# new_base_sensor_1.net
KiCad netlist of a schematic drawn in Altium Designer
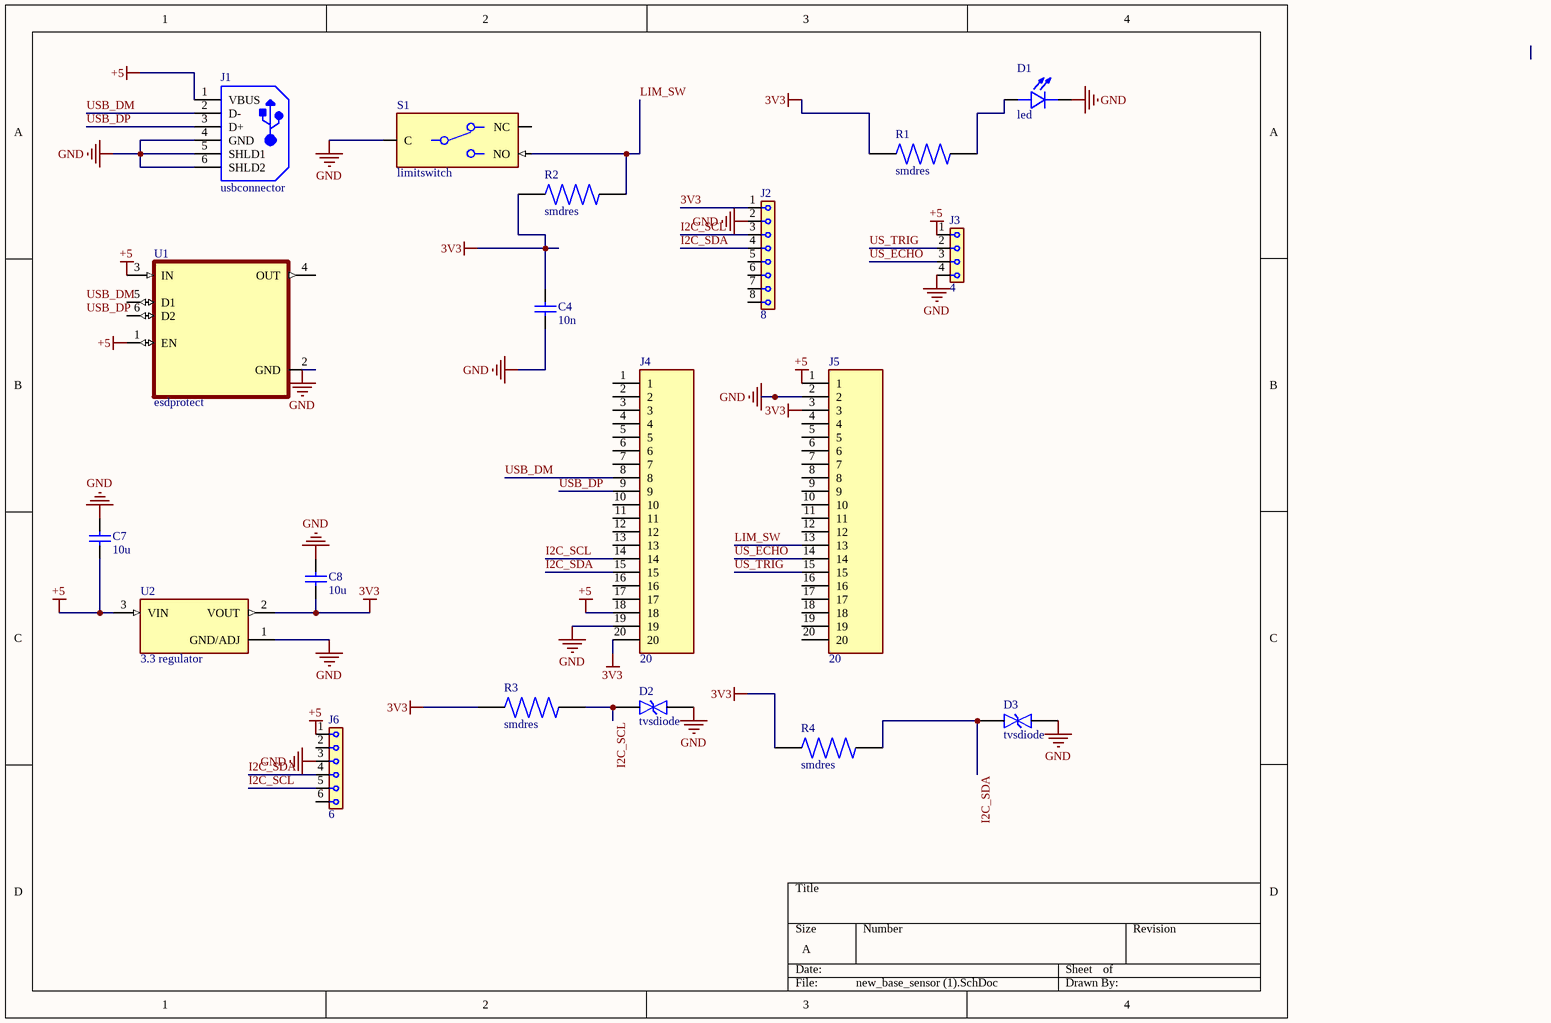
[diagram p0: new_base_sensor (1).SchDoc]

(export (version "E")
  (design (tool "Eeschema 10.0.6"))
  (components
    (comp (ref "C4")
      (value "10n")
      (description "Capacitor")
      (libsource (lib "Simulation Generic Components") (part "Capacitor"))
    )
    (comp (ref "C7")
      (value "10u")
      (description "Capacitor")
      (libsource (lib "Simulation Generic Components") (part "Capacitor"))
    )
    (comp (ref "C8")
      (value "10u")
      (description "Capacitor")
      (libsource (lib "Simulation Generic Components") (part "Capacitor"))
    )
    (comp (ref "D1")
      (value "led")
      (footprint "led")
      (description "Green 1.6 x 0.8 x 0.75 mm (0603) 120 潞 180 mcd Water Clear SMT LED")
      (fields (field (name "MF") "Kingbright") (field (name "MP") "APT1608VGC/A"))
      (libsource (lib "base_sensors") (part "led"))
    )
    (comp (ref "D2")
      (value "tvsdiode")
      (footprint "tvsdiode")
      (description "59V Clamp 169A (8/20Âµs) Ipp Tvs Diode Through Hole DO-201")
      (fields (field (name "MF") "STMicroelectronics") (field (name "MP") "1.5KE33CA"))
      (libsource (lib "base_sensors") (part "tvsdiode"))
    )
    (comp (ref "D3")
      (value "tvsdiode")
      (footprint "tvsdiode")
      (description "59V Clamp 169A (8/20Âµs) Ipp Tvs Diode Through Hole DO-201")
      (fields (field (name "MF") "STMicroelectronics") (field (name "MP") "1.5KE33CA"))
      (libsource (lib "base_sensors") (part "tvsdiode"))
    )
    (comp (ref "J1")
      (value "usbconnector")
      (footprint "usbconnector")
      (description "Single USB 2.0, Receptacle Connecter, B Type, 4 Position Through Hole, -55 to 85 degC, RoHS, Tray")
      (libsource (lib "Actuator_Base_Board") (part "CMP-1752-00001-1"))
    )
    (comp (ref "J2")
      (value "8")
      (footprint "8")
      (fields (field (name "MF") "WÃ¼rth Elektronik") (field (name "MP") "62001011821"))
      (libsource (lib "base_sensors") (part "8"))
    )
    (comp (ref "J3")
      (value "4")
      (footprint "4")
      (fields (field (name "MF") "WÃ¼rth Elektronik") (field (name "MP") "62001011821"))
      (libsource (lib "base_sensors") (part "4"))
    )
    (comp (ref "J4")
      (value "20")
      (footprint "20")
      (description "AMPMODU 20 Position Through-Hole Single Row Straight .100 Inch Header")
      (fields (field (name "MF") "TE Connectivity") (field (name "MP") "2-87224-0"))
      (libsource (lib "base_sensors") (part "20"))
    )
    (comp (ref "J5")
      (value "20")
      (footprint "20")
      (description "AMPMODU 20 Position Through-Hole Single Row Straight .100 Inch Header")
      (fields (field (name "MF") "TE Connectivity") (field (name "MP") "2-87224-0"))
      (libsource (lib "base_sensors") (part "20"))
    )
    (comp (ref "J6")
      (value "6")
      (footprint "6")
      (fields (field (name "MF") "WÃ¼rth Elektronik") (field (name "MP") "62001011821"))
      (libsource (lib "base_sensors") (part "6"))
    )
    (comp (ref "R1")
      (value "smdres")
      (footprint "smdres")
      (description "RES SMD 470 OHM 1% 1/10W 0603")
      (fields (field (name "MF") "Panasonic") (field (name "MP") "ERJS03F4700V"))
      (libsource (lib "new_base_sensors") (part "smdres"))
    )
    (comp (ref "R2")
      (value "smdres")
      (footprint "smdres")
      (description "RES SMD 470 OHM 1% 1/10W 0603")
      (fields (field (name "MF") "Panasonic") (field (name "MP") "ERJS03F4700V"))
      (libsource (lib "new_base_sensors") (part "smdres"))
    )
    (comp (ref "R3")
      (value "smdres")
      (footprint "smdres")
      (description "RES SMD 470 OHM 1% 1/10W 0603")
      (fields (field (name "MF") "Panasonic") (field (name "MP") "ERJS03F4700V"))
      (libsource (lib "new_base_sensors") (part "smdres"))
    )
    (comp (ref "R4")
      (value "smdres")
      (footprint "smdres")
      (description "RES SMD 470 OHM 1% 1/10W 0603")
      (fields (field (name "MF") "Panasonic") (field (name "MP") "ERJS03F4700V"))
      (libsource (lib "new_base_sensors") (part "smdres"))
    )
    (comp (ref "S1")
      (value "limitswitch")
      (footprint "limitswitch")
      (description "Switch Snap Action N.O./N.C. SPDT Long Hinge Lever Solder 5A 250VAC 0.39N Screw Mount")
      (fields (field (name "MF") "Omron") (field (name "MP") "SS-5GL111"))
      (libsource (lib "base_sensors") (part "limitswitch"))
    )
    (comp (ref "U1")
      (value "esdprotect")
      (footprint "esdprotect")
      (description "Current-limit switch and D+/Dâ€“ ESD protection for USB Host")
      (fields (field (name "MF") "Texas Instruments") (field (name "MP") "TPD3S044DBVR"))
      (libsource (lib "base_sensors") (part "esdprotect"))
    )
    (comp (ref "U2")
      (value "3.3 regulator")
      (footprint "3.3regultor")
      (description "LDO Voltage Regulators 800MA LDO LINEAR REG")
      (fields (field (name "MF") "ams AG") (field (name "MP") "AMS1117-3.3"))
      (libsource (lib "base_sensors") (part "3.3 regulator"))
    )
  )
  (nets
    (net (code "1") (name "+5") (class "Default")
      (node (ref "C7") (pin "1") (pinfunction "1_1") (pintype "passive"))
      (node (ref "J1") (pin "1") (pinfunction "VBUS_1") (pintype "passive"))
      (node (ref "J3") (pin "1") (pinfunction "1_1") (pintype "passive"))
      (node (ref "J4") (pin "18") (pinfunction "18_18") (pintype "passive"))
      (node (ref "J5") (pin "1") (pinfunction "1_1") (pintype "passive"))
      (node (ref "J6") (pin "1") (pinfunction "1_1") (pintype "passive"))
      (node (ref "U1") (pin "1") (pinfunction "EN_1") (pintype "bidirectional"))
      (node (ref "U1") (pin "3") (pinfunction "IN_3") (pintype "input"))
      (node (ref "U2") (pin "3") (pinfunction "VIN_3") (pintype "input"))
    )
    (net (code "2") (name "/I2C_SCL") (class "Default")
      (node (ref "D2") (pin "1") (pinfunction "1_1") (pintype "passive"))
      (node (ref "J2") (pin "3") (pinfunction "3_3") (pintype "passive"))
      (node (ref "J4") (pin "14") (pinfunction "14_14") (pintype "passive"))
      (node (ref "J6") (pin "5") (pinfunction "5_5") (pintype "passive"))
      (node (ref "R3") (pin "0") (pinfunction "0_0") (pintype "passive"))
    )
    (net (code "3") (name "/I2C_SDA") (class "Default")
      (node (ref "D3") (pin "1") (pinfunction "1_1") (pintype "passive"))
      (node (ref "J2") (pin "4") (pinfunction "4_4") (pintype "passive"))
      (node (ref "J4") (pin "15") (pinfunction "15_15") (pintype "passive"))
      (node (ref "J6") (pin "4") (pinfunction "4_4") (pintype "passive"))
      (node (ref "R4") (pin "0") (pinfunction "0_0") (pintype "passive"))
    )
    (net (code "4") (name "/LIM_SW") (class "Default")
      (node (ref "J5") (pin "13") (pinfunction "13_13") (pintype "passive"))
      (node (ref "R2") (pin "0") (pinfunction "0_0") (pintype "passive"))
      (node (ref "S1") (pin "NO") (pinfunction "NO_NO") (pintype "input"))
    )
    (net (code "5") (name "/USB_DM") (class "Default")
      (node (ref "J1") (pin "2") (pinfunction "D-_2") (pintype "passive"))
      (node (ref "J4") (pin "8") (pinfunction "8_8") (pintype "passive"))
    )
    (net (code "6") (name "/USB_DP") (class "Default")
      (node (ref "J1") (pin "3") (pinfunction "D+_3") (pintype "passive"))
      (node (ref "J4") (pin "9") (pinfunction "9_9") (pintype "passive"))
    )
    (net (code "7") (name "/US_ECHO") (class "Default")
      (node (ref "J3") (pin "3") (pinfunction "3_3") (pintype "passive"))
      (node (ref "J5") (pin "14") (pinfunction "14_14") (pintype "passive"))
    )
    (net (code "8") (name "/US_TRIG") (class "Default")
      (node (ref "J3") (pin "2") (pinfunction "2_2") (pintype "passive"))
      (node (ref "J5") (pin "15") (pinfunction "15_15") (pintype "passive"))
    )
    (net (code "9") (name "3V3") (class "Default")
      (node (ref "C4") (pin "1") (pinfunction "1_1") (pintype "passive"))
      (node (ref "C8") (pin "1") (pinfunction "1_1") (pintype "passive"))
      (node (ref "J2") (pin "1") (pinfunction "1_1") (pintype "passive"))
      (node (ref "J4") (pin "20") (pinfunction "20_20") (pintype "passive"))
      (node (ref "J5") (pin "3") (pinfunction "3_3") (pintype "passive"))
      (node (ref "R1") (pin "1") (pinfunction "1_1") (pintype "passive"))
      (node (ref "R2") (pin "1") (pinfunction "1_1") (pintype "passive"))
      (node (ref "R3") (pin "1") (pinfunction "1_1") (pintype "passive"))
      (node (ref "R4") (pin "1") (pinfunction "1_1") (pintype "passive"))
      (node (ref "U2") (pin "2") (pinfunction "VOUT_2") (pintype "output"))
    )
    (net (code "10") (name "GND") (class "Default")
      (node (ref "C4") (pin "2") (pinfunction "2_2") (pintype "passive"))
      (node (ref "C7") (pin "2") (pinfunction "2_2") (pintype "passive"))
      (node (ref "C8") (pin "2") (pinfunction "2_2") (pintype "passive"))
      (node (ref "D1") (pin "C") (pinfunction "C_C") (pintype "passive"))
      (node (ref "D2") (pin "2") (pinfunction "2_2") (pintype "passive"))
      (node (ref "D3") (pin "2") (pinfunction "2_2") (pintype "passive"))
      (node (ref "J1") (pin "4") (pinfunction "GND_4") (pintype "passive"))
      (node (ref "J1") (pin "5") (pinfunction "SHLD1_5") (pintype "passive"))
      (node (ref "J1") (pin "6") (pinfunction "SHLD2_6") (pintype "passive"))
      (node (ref "J2") (pin "2") (pinfunction "2_2") (pintype "passive"))
      (node (ref "J3") (pin "4") (pinfunction "4_4") (pintype "passive"))
      (node (ref "J4") (pin "19") (pinfunction "19_19") (pintype "passive"))
      (node (ref "J5") (pin "2") (pinfunction "2_2") (pintype "passive"))
      (node (ref "J6") (pin "3") (pinfunction "3_3") (pintype "passive"))
      (node (ref "S1") (pin "C") (pinfunction "C_C") (pintype "bidirectional"))
      (node (ref "U1") (pin "2") (pinfunction "GND_2") (pintype "power_in"))
      (node (ref "U2") (pin "1") (pinfunction "GND/ADJ_1") (pintype "power_in"))
    )
    (net (code "11") (name "Net-(D1-PadA)") (class "Default")
      (node (ref "D1") (pin "A") (pinfunction "A_A") (pintype "passive"))
      (node (ref "R1") (pin "0") (pinfunction "0_0") (pintype "passive"))
    )
    (net (code "12") (name "unconnected-(J2-Pad5)") (class "Default")
      (node (ref "J2") (pin "5") (pinfunction "5_5") (pintype "passive"))
    )
    (net (code "13") (name "unconnected-(J2-Pad6)") (class "Default")
      (node (ref "J2") (pin "6") (pinfunction "6_6") (pintype "passive"))
    )
    (net (code "14") (name "unconnected-(J2-Pad7)") (class "Default")
      (node (ref "J2") (pin "7") (pinfunction "7_7") (pintype "passive"))
    )
    (net (code "15") (name "unconnected-(J2-Pad8)") (class "Default")
      (node (ref "J2") (pin "8") (pinfunction "8_8") (pintype "passive"))
    )
    (net (code "16") (name "unconnected-(J4-Pad1)") (class "Default")
      (node (ref "J4") (pin "1") (pinfunction "1_1") (pintype "passive"))
    )
    (net (code "17") (name "unconnected-(J4-Pad2)") (class "Default")
      (node (ref "J4") (pin "2") (pinfunction "2_2") (pintype "passive"))
    )
    (net (code "18") (name "unconnected-(J4-Pad3)") (class "Default")
      (node (ref "J4") (pin "3") (pinfunction "3_3") (pintype "passive"))
    )
    (net (code "19") (name "unconnected-(J4-Pad4)") (class "Default")
      (node (ref "J4") (pin "4") (pinfunction "4_4") (pintype "passive"))
    )
    (net (code "20") (name "unconnected-(J4-Pad5)") (class "Default")
      (node (ref "J4") (pin "5") (pinfunction "5_5") (pintype "passive"))
    )
    (net (code "21") (name "unconnected-(J4-Pad6)") (class "Default")
      (node (ref "J4") (pin "6") (pinfunction "6_6") (pintype "passive"))
    )
    (net (code "22") (name "unconnected-(J4-Pad7)") (class "Default")
      (node (ref "J4") (pin "7") (pinfunction "7_7") (pintype "passive"))
    )
    (net (code "23") (name "unconnected-(J4-Pad10)") (class "Default")
      (node (ref "J4") (pin "10") (pinfunction "10_10") (pintype "passive"))
    )
    (net (code "24") (name "unconnected-(J4-Pad11)") (class "Default")
      (node (ref "J4") (pin "11") (pinfunction "11_11") (pintype "passive"))
    )
    (net (code "25") (name "unconnected-(J4-Pad12)") (class "Default")
      (node (ref "J4") (pin "12") (pinfunction "12_12") (pintype "passive"))
    )
    (net (code "26") (name "unconnected-(J4-Pad13)") (class "Default")
      (node (ref "J4") (pin "13") (pinfunction "13_13") (pintype "passive"))
    )
    (net (code "27") (name "unconnected-(J4-Pad16)") (class "Default")
      (node (ref "J4") (pin "16") (pinfunction "16_16") (pintype "passive"))
    )
    (net (code "28") (name "unconnected-(J4-Pad17)") (class "Default")
      (node (ref "J4") (pin "17") (pinfunction "17_17") (pintype "passive"))
    )
    (net (code "29") (name "unconnected-(J5-Pad4)") (class "Default")
      (node (ref "J5") (pin "4") (pinfunction "4_4") (pintype "passive"))
    )
    (net (code "30") (name "unconnected-(J5-Pad5)") (class "Default")
      (node (ref "J5") (pin "5") (pinfunction "5_5") (pintype "passive"))
    )
    (net (code "31") (name "unconnected-(J5-Pad6)") (class "Default")
      (node (ref "J5") (pin "6") (pinfunction "6_6") (pintype "passive"))
    )
    (net (code "32") (name "unconnected-(J5-Pad7)") (class "Default")
      (node (ref "J5") (pin "7") (pinfunction "7_7") (pintype "passive"))
    )
    (net (code "33") (name "unconnected-(J5-Pad8)") (class "Default")
      (node (ref "J5") (pin "8") (pinfunction "8_8") (pintype "passive"))
    )
    (net (code "34") (name "unconnected-(J5-Pad9)") (class "Default")
      (node (ref "J5") (pin "9") (pinfunction "9_9") (pintype "passive"))
    )
    (net (code "35") (name "unconnected-(J5-Pad10)") (class "Default")
      (node (ref "J5") (pin "10") (pinfunction "10_10") (pintype "passive"))
    )
    (net (code "36") (name "unconnected-(J5-Pad11)") (class "Default")
      (node (ref "J5") (pin "11") (pinfunction "11_11") (pintype "passive"))
    )
    (net (code "37") (name "unconnected-(J5-Pad12)") (class "Default")
      (node (ref "J5") (pin "12") (pinfunction "12_12") (pintype "passive"))
    )
    (net (code "38") (name "unconnected-(J5-Pad16)") (class "Default")
      (node (ref "J5") (pin "16") (pinfunction "16_16") (pintype "passive"))
    )
    (net (code "39") (name "unconnected-(J5-Pad17)") (class "Default")
      (node (ref "J5") (pin "17") (pinfunction "17_17") (pintype "passive"))
    )
    (net (code "40") (name "unconnected-(J5-Pad18)") (class "Default")
      (node (ref "J5") (pin "18") (pinfunction "18_18") (pintype "passive"))
    )
    (net (code "41") (name "unconnected-(J5-Pad19)") (class "Default")
      (node (ref "J5") (pin "19") (pinfunction "19_19") (pintype "passive"))
    )
    (net (code "42") (name "unconnected-(J5-Pad20)") (class "Default")
      (node (ref "J5") (pin "20") (pinfunction "20_20") (pintype "passive"))
    )
    (net (code "43") (name "unconnected-(J6-Pad2)") (class "Default")
      (node (ref "J6") (pin "2") (pinfunction "2_2") (pintype "passive"))
    )
    (net (code "44") (name "unconnected-(J6-Pad6)") (class "Default")
      (node (ref "J6") (pin "6") (pinfunction "6_6") (pintype "passive"))
    )
    (net (code "45") (name "unconnected-(S1-PadNC)") (class "Default")
      (node (ref "S1") (pin "NC") (pinfunction "NC_NC") (pintype "bidirectional"))
    )
    (net (code "46") (name "unconnected-(U1-D1-Pad5)") (class "Default")
      (node (ref "U1") (pin "5") (pinfunction "D1_5") (pintype "bidirectional"))
    )
    (net (code "47") (name "unconnected-(U1-D2-Pad6)") (class "Default")
      (node (ref "U1") (pin "6") (pinfunction "D2_6") (pintype "bidirectional"))
    )
    (net (code "48") (name "unconnected-(U1-OUT-Pad4)") (class "Default")
      (node (ref "U1") (pin "4") (pinfunction "OUT_4") (pintype "output"))
    )
  )
)
